# untitled_-_5.net
KiCad netlist of a schematic drawn in EAGLE
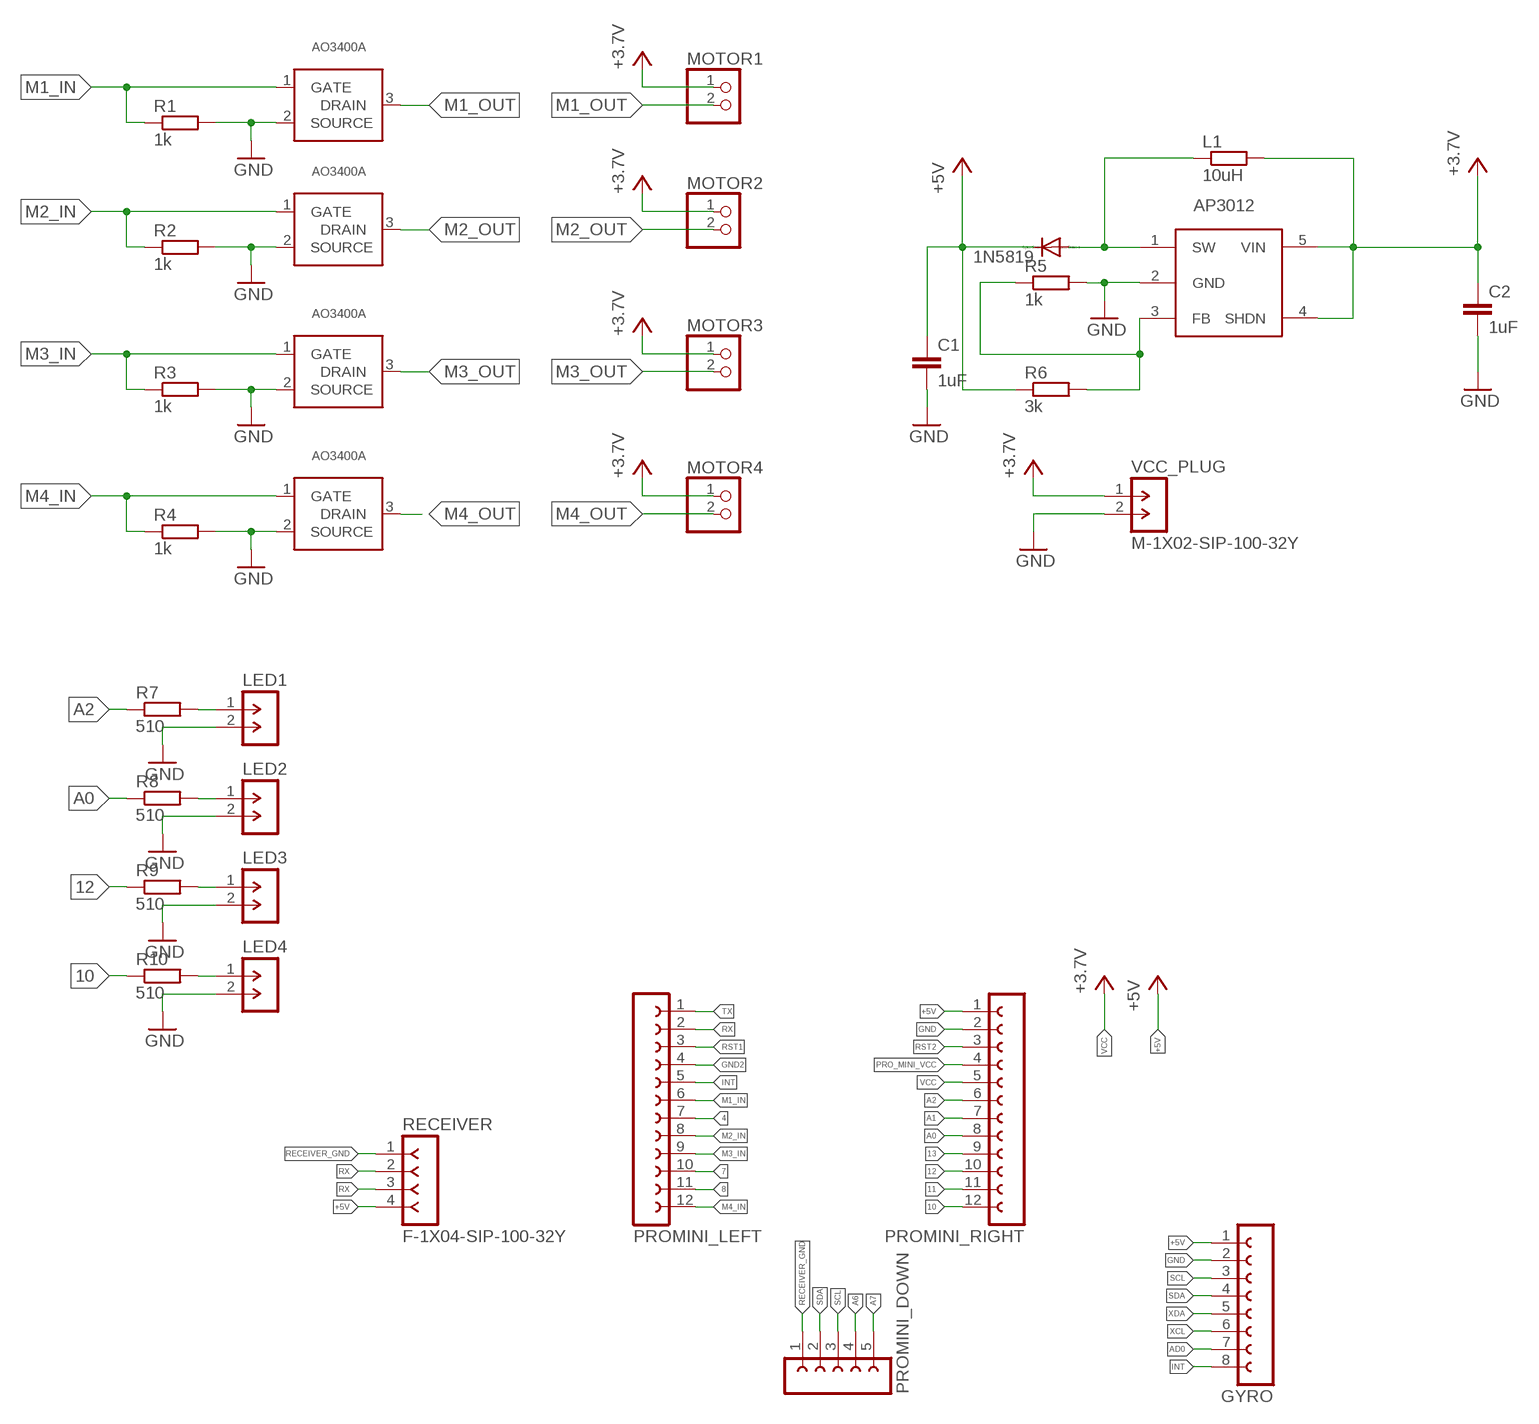
[diagram p0: schematic, sheet 1]

(export (version "E")
  (design (tool "Eeschema 10.0.6"))
  (components
    (comp (ref "1N5819")
      (value "DIODE-DO214AC")
      (footprint "eagle-import:DO214AC")
      (libsource (lib "eagle-import") (part "DIODE-DO214AC"))
    )
    (comp (ref "C1")
      (value "1uF")
      (footprint "eagle-import:C1206")
      (libsource (lib "eagle-import") (part "C-EUC1206"))
    )
    (comp (ref "C2")
      (value "1uF")
      (footprint "eagle-import:C1206")
      (libsource (lib "eagle-import") (part "C-EUC1206"))
    )
    (comp (ref "GYRO")
      (value "FE08-1")
      (footprint "eagle-import:FE08")
      (libsource (lib "eagle-import") (part "FE08-1"))
    )
    (comp (ref "L1")
      (value "10uH")
      (footprint "eagle-import:R0805")
      (libsource (lib "eagle-import") (part "R-EU_R0805"))
    )
    (comp (ref "LED1")
      (value "M-1X02-SIP-100-32Y")
      (footprint "eagle-import:SIP-100-02-32Y")
      (libsource (lib "eagle-import") (part "M-1X02-SIP-100-32Y"))
    )
    (comp (ref "LED2")
      (value "M-1X02-SIP-100-32Y")
      (footprint "eagle-import:SIP-100-02-32Y")
      (libsource (lib "eagle-import") (part "M-1X02-SIP-100-32Y"))
    )
    (comp (ref "LED3")
      (value "M-1X02-SIP-100-32Y")
      (footprint "eagle-import:SIP-100-02-32Y")
      (libsource (lib "eagle-import") (part "M-1X02-SIP-100-32Y"))
    )
    (comp (ref "LED4")
      (value "M-1X02-SIP-100-32Y")
      (footprint "eagle-import:SIP-100-02-32Y")
      (libsource (lib "eagle-import") (part "M-1X02-SIP-100-32Y"))
    )
    (comp (ref "M1_DRV")
      (value "AO3400A")
      (footprint "eagle-import:SOT-23")
      (libsource (lib "eagle-import") (part "AO3400A"))
    )
    (comp (ref "M2_DRV")
      (value "AO3400A")
      (footprint "eagle-import:SOT-23")
      (libsource (lib "eagle-import") (part "AO3400A"))
    )
    (comp (ref "M3_DRV")
      (value "AO3400A")
      (footprint "eagle-import:SOT-23")
      (libsource (lib "eagle-import") (part "AO3400A"))
    )
    (comp (ref "M4_DRV")
      (value "AO3400A")
      (footprint "eagle-import:SOT-23")
      (libsource (lib "eagle-import") (part "AO3400A"))
    )
    (comp (ref "MOTOR1")
      (value "PINHD-1X2")
      (footprint "eagle-import:1X02")
      (libsource (lib "eagle-import") (part "PINHD-1X2"))
    )
    (comp (ref "MOTOR2")
      (value "PINHD-1X2")
      (footprint "eagle-import:1X02")
      (libsource (lib "eagle-import") (part "PINHD-1X2"))
    )
    (comp (ref "MOTOR3")
      (value "PINHD-1X2")
      (footprint "eagle-import:1X02")
      (libsource (lib "eagle-import") (part "PINHD-1X2"))
    )
    (comp (ref "MOTOR4")
      (value "PINHD-1X2")
      (footprint "eagle-import:1X02")
      (libsource (lib "eagle-import") (part "PINHD-1X2"))
    )
    (comp (ref "PROMINI_DOWN")
      (value "FE05-1")
      (footprint "eagle-import:FE05-1")
      (libsource (lib "eagle-import") (part "FE05-1"))
    )
    (comp (ref "PROMINI_LEFT")
      (value "FE12-1")
      (footprint "eagle-import:FE12")
      (libsource (lib "eagle-import") (part "FE12-1"))
    )
    (comp (ref "PROMINI_RIGHT")
      (value "FE12-1")
      (footprint "eagle-import:FE12")
      (libsource (lib "eagle-import") (part "FE12-1"))
    )
    (comp (ref "R1")
      (value "1k")
      (footprint "eagle-import:R1206")
      (libsource (lib "eagle-import") (part "R-EU_R1206"))
    )
    (comp (ref "R2")
      (value "1k")
      (footprint "eagle-import:R1206")
      (libsource (lib "eagle-import") (part "R-EU_R1206"))
    )
    (comp (ref "R3")
      (value "1k")
      (footprint "eagle-import:R1206")
      (libsource (lib "eagle-import") (part "R-EU_R1206"))
    )
    (comp (ref "R4")
      (value "1k")
      (footprint "eagle-import:R1206")
      (libsource (lib "eagle-import") (part "R-EU_R1206"))
    )
    (comp (ref "R5")
      (value "1k")
      (footprint "eagle-import:R1206")
      (libsource (lib "eagle-import") (part "R-EU_R1206"))
    )
    (comp (ref "R6")
      (value "3k")
      (footprint "eagle-import:R1206")
      (libsource (lib "eagle-import") (part "R-EU_R1206"))
    )
    (comp (ref "R7")
      (value "510")
      (footprint "eagle-import:R0805")
      (libsource (lib "eagle-import") (part "R-EU_R0805"))
    )
    (comp (ref "R8")
      (value "510")
      (footprint "eagle-import:R0805")
      (libsource (lib "eagle-import") (part "R-EU_R0805"))
    )
    (comp (ref "R9")
      (value "510")
      (footprint "eagle-import:R0805")
      (libsource (lib "eagle-import") (part "R-EU_R0805"))
    )
    (comp (ref "R10")
      (value "510")
      (footprint "eagle-import:R0805")
      (libsource (lib "eagle-import") (part "R-EU_R0805"))
    )
    (comp (ref "RECEIVER")
      (value "F-1X04-SIP-100-32Y")
      (footprint "eagle-import:SIP-100-04-32Y")
      (libsource (lib "eagle-import") (part "F-1X04-SIP-100-32Y"))
    )
    (comp (ref "U$5")
      (value "AP3012")
      (footprint "eagle-import:SOT-23-5")
      (libsource (lib "eagle-import") (part "AP3012"))
    )
    (comp (ref "VCC_PLUG")
      (value "M-1X02-SIP-100-32Y")
      (footprint "eagle-import:SIP-100-02-32Y")
      (libsource (lib "eagle-import") (part "M-1X02-SIP-100-32Y"))
    )
  )
  (nets
    (net (code "1") (name "+5V") (class "Default")
      (node (ref "1N5819") (pin "C") (pinfunction "C_C") (pintype "passive"))
      (node (ref "C1") (pin "1") (pinfunction "1_1") (pintype "passive"))
      (node (ref "GYRO") (pin "1") (pinfunction "1_1") (pintype "passive"))
      (node (ref "PROMINI_RIGHT") (pin "1") (pinfunction "1_1") (pintype "passive"))
      (node (ref "R6") (pin "1") (pinfunction "1_1") (pintype "passive"))
      (node (ref "RECEIVER") (pin "4") (pinfunction "4_4") (pintype "passive"))
    )
    (net (code "2") (name "4") (class "Default")
      (node (ref "PROMINI_LEFT") (pin "7") (pinfunction "7_7") (pintype "passive"))
    )
    (net (code "3") (name "7") (class "Default")
      (node (ref "PROMINI_LEFT") (pin "10") (pinfunction "10_10") (pintype "passive"))
    )
    (net (code "4") (name "8") (class "Default")
      (node (ref "PROMINI_LEFT") (pin "11") (pinfunction "11_11") (pintype "passive"))
    )
    (net (code "5") (name "10") (class "Default")
      (node (ref "PROMINI_RIGHT") (pin "12") (pinfunction "12_12") (pintype "passive"))
      (node (ref "R10") (pin "1") (pinfunction "1_1") (pintype "passive"))
    )
    (net (code "6") (name "11") (class "Default")
      (node (ref "PROMINI_RIGHT") (pin "11") (pinfunction "11_11") (pintype "passive"))
    )
    (net (code "7") (name "12") (class "Default")
      (node (ref "PROMINI_RIGHT") (pin "10") (pinfunction "10_10") (pintype "passive"))
      (node (ref "R9") (pin "1") (pinfunction "1_1") (pintype "passive"))
    )
    (net (code "8") (name "13") (class "Default")
      (node (ref "PROMINI_RIGHT") (pin "9") (pinfunction "9_9") (pintype "passive"))
    )
    (net (code "9") (name "A0") (class "Default")
      (node (ref "PROMINI_RIGHT") (pin "8") (pinfunction "8_8") (pintype "passive"))
      (node (ref "R8") (pin "1") (pinfunction "1_1") (pintype "passive"))
    )
    (net (code "10") (name "A1") (class "Default")
      (node (ref "PROMINI_RIGHT") (pin "7") (pinfunction "7_7") (pintype "passive"))
    )
    (net (code "11") (name "A2") (class "Default")
      (node (ref "PROMINI_RIGHT") (pin "6") (pinfunction "6_6") (pintype "passive"))
      (node (ref "R7") (pin "1") (pinfunction "1_1") (pintype "passive"))
    )
    (net (code "12") (name "A6") (class "Default")
      (node (ref "PROMINI_DOWN") (pin "4") (pinfunction "4_4") (pintype "passive"))
    )
    (net (code "13") (name "A7") (class "Default")
      (node (ref "PROMINI_DOWN") (pin "5") (pinfunction "5_5") (pintype "passive"))
    )
    (net (code "14") (name "AD0") (class "Default")
      (node (ref "GYRO") (pin "7") (pinfunction "7_7") (pintype "passive"))
    )
    (net (code "15") (name "GND") (class "Default")
      (node (ref "C1") (pin "2") (pinfunction "2_2") (pintype "passive"))
      (node (ref "C2") (pin "2") (pinfunction "2_2") (pintype "passive"))
      (node (ref "GYRO") (pin "2") (pinfunction "2_2") (pintype "passive"))
      (node (ref "LED1") (pin "2") (pinfunction "2_2") (pintype "passive"))
      (node (ref "LED2") (pin "2") (pinfunction "2_2") (pintype "passive"))
      (node (ref "LED3") (pin "2") (pinfunction "2_2") (pintype "passive"))
      (node (ref "LED4") (pin "2") (pinfunction "2_2") (pintype "passive"))
      (node (ref "M1_DRV") (pin "2") (pinfunction "SOURCE_2") (pintype "bidirectional"))
      (node (ref "M2_DRV") (pin "2") (pinfunction "SOURCE_2") (pintype "bidirectional"))
      (node (ref "M3_DRV") (pin "2") (pinfunction "SOURCE_2") (pintype "bidirectional"))
      (node (ref "M4_DRV") (pin "2") (pinfunction "SOURCE_2") (pintype "bidirectional"))
      (node (ref "PROMINI_RIGHT") (pin "2") (pinfunction "2_2") (pintype "passive"))
      (node (ref "R1") (pin "2") (pinfunction "2_2") (pintype "passive"))
      (node (ref "R2") (pin "2") (pinfunction "2_2") (pintype "passive"))
      (node (ref "R3") (pin "2") (pinfunction "2_2") (pintype "passive"))
      (node (ref "R4") (pin "2") (pinfunction "2_2") (pintype "passive"))
      (node (ref "R5") (pin "2") (pinfunction "2_2") (pintype "passive"))
      (node (ref "U$5") (pin "2") (pinfunction "GND_2") (pintype "bidirectional"))
      (node (ref "VCC_PLUG") (pin "2") (pinfunction "2_2") (pintype "passive"))
    )
    (net (code "16") (name "GND2") (class "Default")
      (node (ref "PROMINI_LEFT") (pin "4") (pinfunction "4_4") (pintype "passive"))
    )
    (net (code "17") (name "INT") (class "Default")
      (node (ref "GYRO") (pin "8") (pinfunction "8_8") (pintype "passive"))
      (node (ref "PROMINI_LEFT") (pin "5") (pinfunction "5_5") (pintype "passive"))
    )
    (net (code "18") (name "M1_IN") (class "Default")
      (node (ref "M1_DRV") (pin "1") (pinfunction "GATE_1") (pintype "bidirectional"))
      (node (ref "PROMINI_LEFT") (pin "6") (pinfunction "6_6") (pintype "passive"))
      (node (ref "R1") (pin "1") (pinfunction "1_1") (pintype "passive"))
    )
    (net (code "19") (name "M1_OUT") (class "Default")
      (node (ref "M1_DRV") (pin "3") (pinfunction "DRAIN_3") (pintype "bidirectional"))
      (node (ref "MOTOR1") (pin "2") (pinfunction "2_2") (pintype "passive"))
    )
    (net (code "20") (name "M2_IN") (class "Default")
      (node (ref "M2_DRV") (pin "1") (pinfunction "GATE_1") (pintype "bidirectional"))
      (node (ref "PROMINI_LEFT") (pin "8") (pinfunction "8_8") (pintype "passive"))
      (node (ref "R2") (pin "1") (pinfunction "1_1") (pintype "passive"))
    )
    (net (code "21") (name "M2_OUT") (class "Default")
      (node (ref "M2_DRV") (pin "3") (pinfunction "DRAIN_3") (pintype "bidirectional"))
      (node (ref "MOTOR2") (pin "2") (pinfunction "2_2") (pintype "passive"))
    )
    (net (code "22") (name "M3_IN") (class "Default")
      (node (ref "M3_DRV") (pin "1") (pinfunction "GATE_1") (pintype "bidirectional"))
      (node (ref "PROMINI_LEFT") (pin "9") (pinfunction "9_9") (pintype "passive"))
      (node (ref "R3") (pin "1") (pinfunction "1_1") (pintype "passive"))
    )
    (net (code "23") (name "M3_OUT") (class "Default")
      (node (ref "M3_DRV") (pin "3") (pinfunction "DRAIN_3") (pintype "bidirectional"))
      (node (ref "MOTOR3") (pin "2") (pinfunction "2_2") (pintype "passive"))
    )
    (net (code "24") (name "M4_IN") (class "Default")
      (node (ref "M4_DRV") (pin "1") (pinfunction "GATE_1") (pintype "bidirectional"))
      (node (ref "PROMINI_LEFT") (pin "12") (pinfunction "12_12") (pintype "passive"))
      (node (ref "R4") (pin "1") (pinfunction "1_1") (pintype "passive"))
    )
    (net (code "25") (name "M4_OUT") (class "Default")
      (node (ref "M4_DRV") (pin "3") (pinfunction "DRAIN_3") (pintype "bidirectional"))
      (node (ref "MOTOR4") (pin "2") (pinfunction "2_2") (pintype "passive"))
    )
    (net (code "26") (name "Net-(LED1-Pad1)") (class "Default")
      (node (ref "LED1") (pin "1") (pinfunction "1_1") (pintype "passive"))
      (node (ref "R7") (pin "2") (pinfunction "2_2") (pintype "passive"))
    )
    (net (code "27") (name "Net-(LED2-Pad1)") (class "Default")
      (node (ref "LED2") (pin "1") (pinfunction "1_1") (pintype "passive"))
      (node (ref "R8") (pin "2") (pinfunction "2_2") (pintype "passive"))
    )
    (net (code "28") (name "Net-(LED3-Pad1)") (class "Default")
      (node (ref "LED3") (pin "1") (pinfunction "1_1") (pintype "passive"))
      (node (ref "R9") (pin "2") (pinfunction "2_2") (pintype "passive"))
    )
    (net (code "29") (name "Net-(LED4-Pad1)") (class "Default")
      (node (ref "LED4") (pin "1") (pinfunction "1_1") (pintype "passive"))
      (node (ref "R10") (pin "2") (pinfunction "2_2") (pintype "passive"))
    )
    (net (code "30") (name "Net-(U$5-FB)") (class "Default")
      (node (ref "R5") (pin "1") (pinfunction "1_1") (pintype "passive"))
      (node (ref "R6") (pin "2") (pinfunction "2_2") (pintype "passive"))
      (node (ref "U$5") (pin "3") (pinfunction "FB_3") (pintype "bidirectional"))
    )
    (net (code "31") (name "Net-(U$5-SW)") (class "Default")
      (node (ref "1N5819") (pin "A") (pinfunction "A_A") (pintype "passive"))
      (node (ref "L1") (pin "1") (pinfunction "1_1") (pintype "passive"))
      (node (ref "U$5") (pin "1") (pinfunction "SW_1") (pintype "bidirectional"))
    )
    (net (code "32") (name "PRO_MINI_VCC") (class "Default")
      (node (ref "PROMINI_RIGHT") (pin "4") (pinfunction "4_4") (pintype "passive"))
    )
    (net (code "33") (name "RECEIVER_GND") (class "Default")
      (node (ref "PROMINI_DOWN") (pin "1") (pinfunction "1_1") (pintype "passive"))
      (node (ref "RECEIVER") (pin "1") (pinfunction "1_1") (pintype "passive"))
    )
    (net (code "34") (name "RST1") (class "Default")
      (node (ref "PROMINI_LEFT") (pin "3") (pinfunction "3_3") (pintype "passive"))
    )
    (net (code "35") (name "RST2") (class "Default")
      (node (ref "PROMINI_RIGHT") (pin "3") (pinfunction "3_3") (pintype "passive"))
    )
    (net (code "36") (name "RX") (class "Default")
      (node (ref "PROMINI_LEFT") (pin "2") (pinfunction "2_2") (pintype "passive"))
      (node (ref "RECEIVER") (pin "2") (pinfunction "2_2") (pintype "passive"))
      (node (ref "RECEIVER") (pin "3") (pinfunction "3_3") (pintype "passive"))
    )
    (net (code "37") (name "SCL") (class "Default")
      (node (ref "GYRO") (pin "3") (pinfunction "3_3") (pintype "passive"))
      (node (ref "PROMINI_DOWN") (pin "3") (pinfunction "3_3") (pintype "passive"))
    )
    (net (code "38") (name "SDA") (class "Default")
      (node (ref "GYRO") (pin "4") (pinfunction "4_4") (pintype "passive"))
      (node (ref "PROMINI_DOWN") (pin "2") (pinfunction "2_2") (pintype "passive"))
    )
    (net (code "39") (name "TX") (class "Default")
      (node (ref "PROMINI_LEFT") (pin "1") (pinfunction "1_1") (pintype "passive"))
    )
    (net (code "40") (name "VCC") (class "Default")
      (node (ref "C2") (pin "1") (pinfunction "1_1") (pintype "passive"))
      (node (ref "L1") (pin "2") (pinfunction "2_2") (pintype "passive"))
      (node (ref "MOTOR1") (pin "1") (pinfunction "1_1") (pintype "passive"))
      (node (ref "MOTOR2") (pin "1") (pinfunction "1_1") (pintype "passive"))
      (node (ref "MOTOR3") (pin "1") (pinfunction "1_1") (pintype "passive"))
      (node (ref "MOTOR4") (pin "1") (pinfunction "1_1") (pintype "passive"))
      (node (ref "PROMINI_RIGHT") (pin "5") (pinfunction "5_5") (pintype "passive"))
      (node (ref "U$5") (pin "4") (pinfunction "SHDN_4") (pintype "bidirectional"))
      (node (ref "U$5") (pin "5") (pinfunction "VIN_5") (pintype "bidirectional"))
      (node (ref "VCC_PLUG") (pin "1") (pinfunction "1_1") (pintype "passive"))
    )
    (net (code "41") (name "XCL") (class "Default")
      (node (ref "GYRO") (pin "6") (pinfunction "6_6") (pintype "passive"))
    )
    (net (code "42") (name "XDA") (class "Default")
      (node (ref "GYRO") (pin "5") (pinfunction "5_5") (pintype "passive"))
    )
  )
)
